# ETH_PHY.net
KiCad netlist of a schematic drawn in Altium Designer
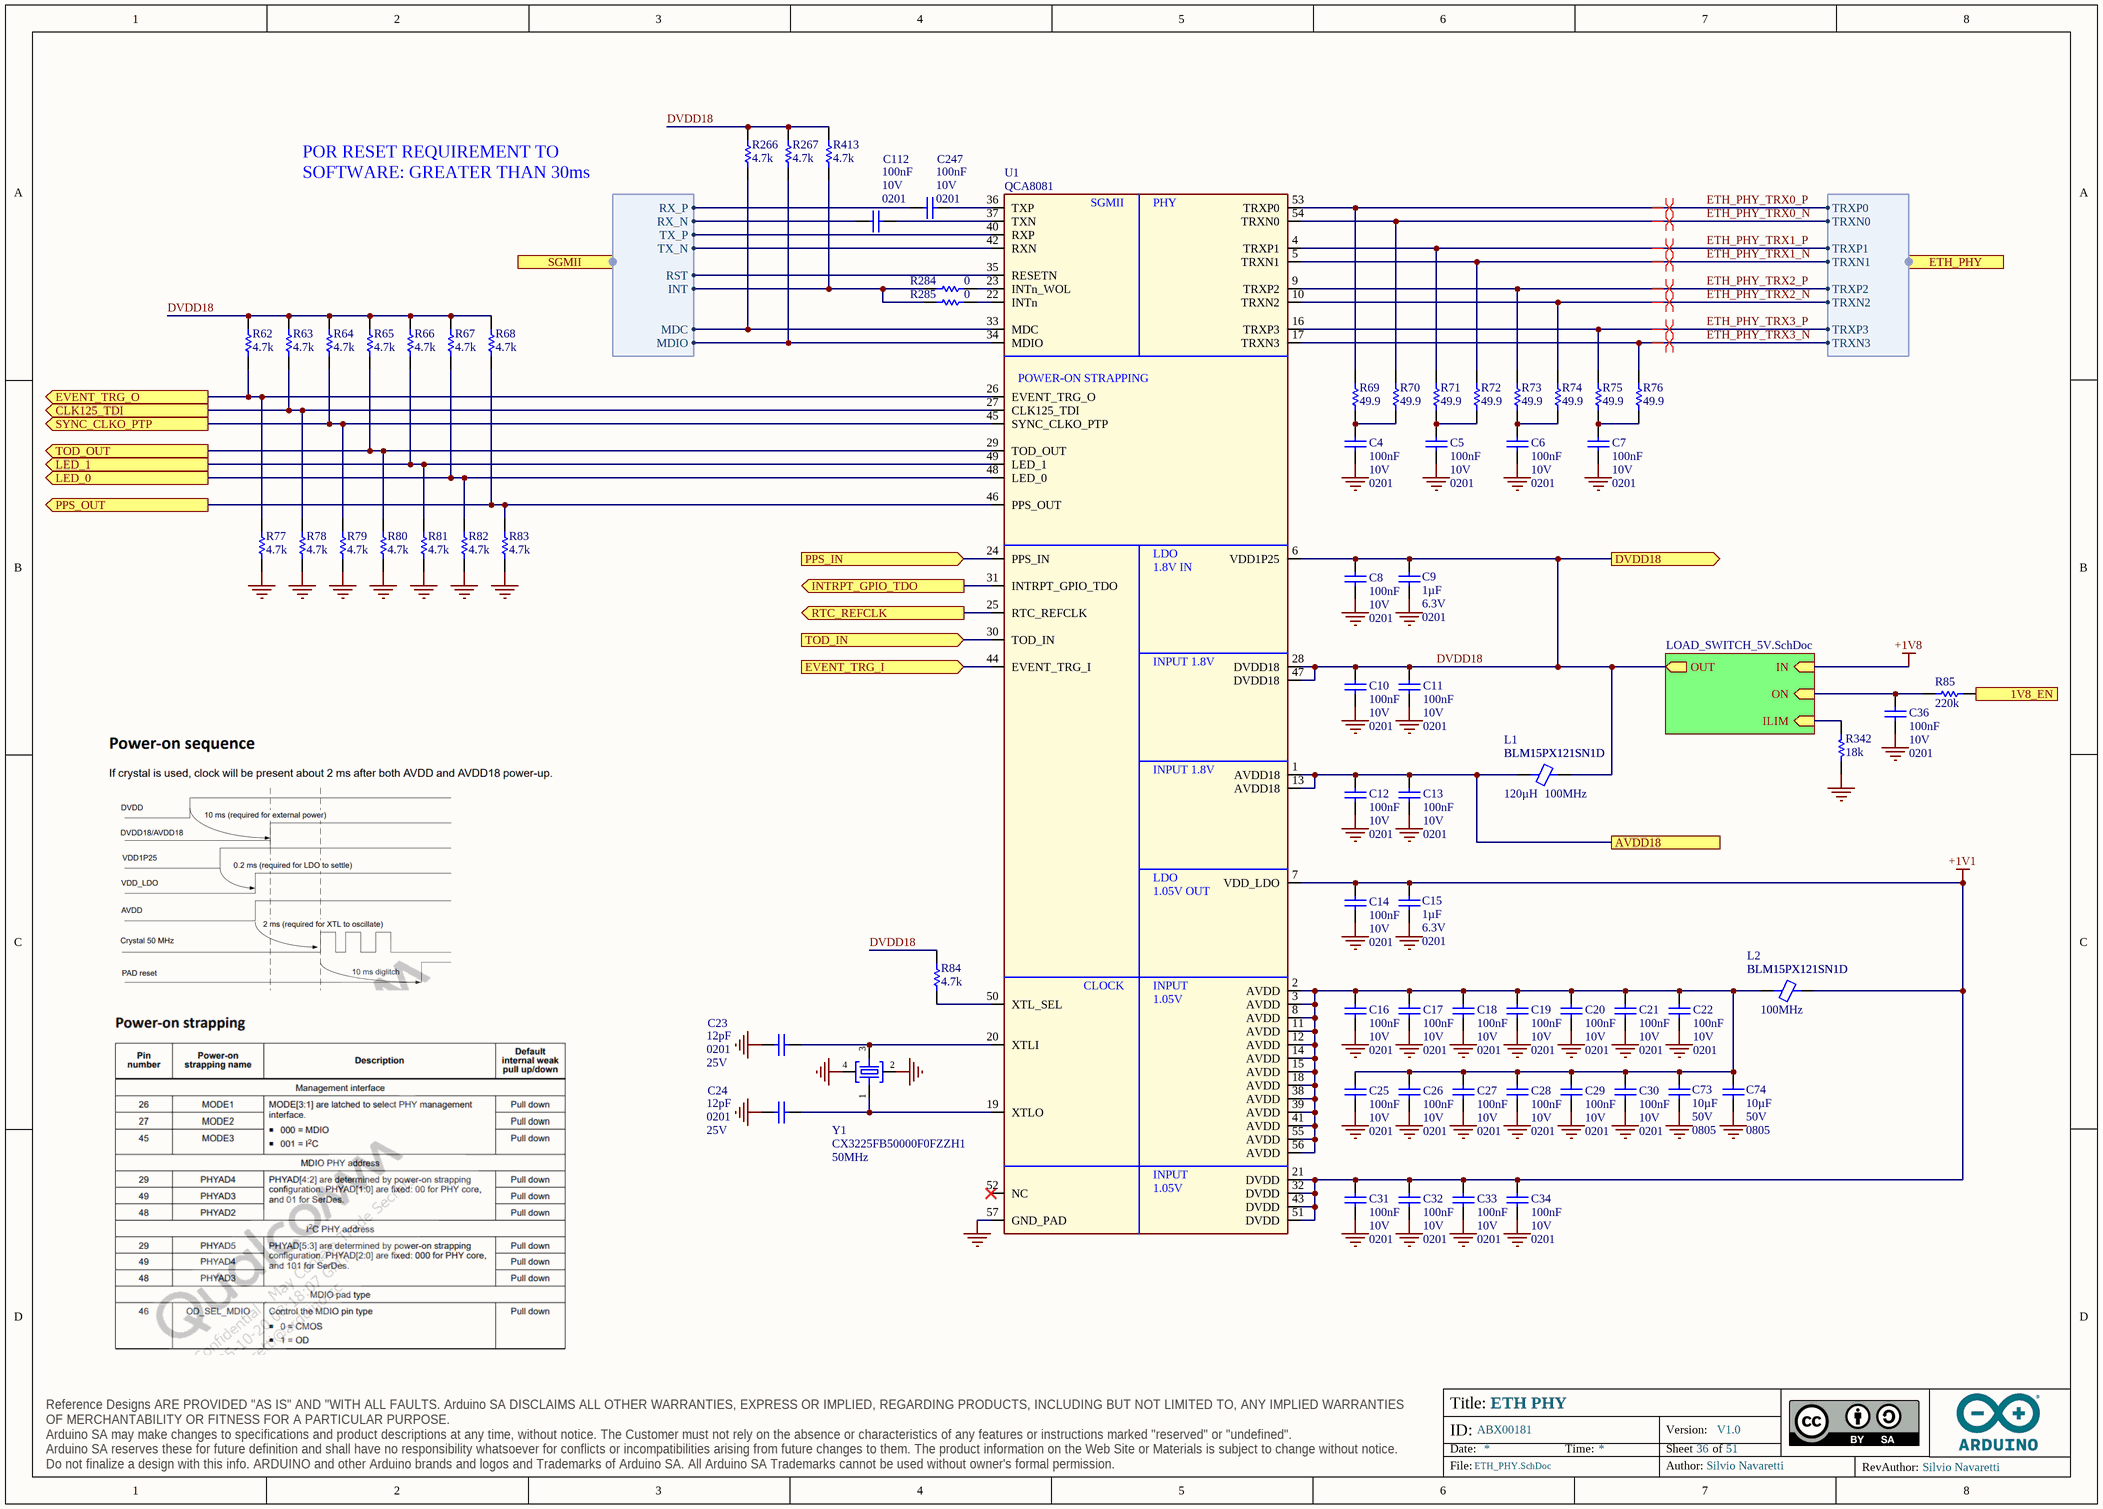
[diagram p0: ETH_PHY.SchDoc]

(export (version "E")
  (design (tool "Eeschema 10.0.6"))
  (components
    (comp (ref "C4")
      (value "100nF")
      (footprint "CAP-0201")
      (description "CAP CHIP 0201 100nF 10% 10V X5R")
      (fields
        (field (name "PART NUMBER") "CL03A104KP3NNNC")
        (field (name "MANUFACTURER") "Samsung Electro-Mechanics")
        (field (name "VOLTAGE") "10V")
        (field (name "CASE CODE (IMPERIAL)") "0201")
      )
      (libsource (lib "Clean") (part "CAP"))
    )
    (comp (ref "C5")
      (value "100nF")
      (footprint "CAP-0201")
      (description "CAP CHIP 0201 100nF 10% 10V X5R")
      (fields
        (field (name "PART NUMBER") "CL03A104KP3NNNC")
        (field (name "MANUFACTURER") "Samsung Electro-Mechanics")
        (field (name "VOLTAGE") "10V")
        (field (name "CASE CODE (IMPERIAL)") "0201")
      )
      (libsource (lib "Clean") (part "CAP"))
    )
    (comp (ref "C6")
      (value "100nF")
      (footprint "CAP-0201")
      (description "CAP CHIP 0201 100nF 10% 10V X5R")
      (fields
        (field (name "PART NUMBER") "CL03A104KP3NNNC")
        (field (name "MANUFACTURER") "Samsung Electro-Mechanics")
        (field (name "VOLTAGE") "10V")
        (field (name "CASE CODE (IMPERIAL)") "0201")
      )
      (libsource (lib "Clean") (part "CAP"))
    )
    (comp (ref "C7")
      (value "100nF")
      (footprint "CAP-0201")
      (description "CAP CHIP 0201 100nF 10% 10V X5R")
      (fields
        (field (name "PART NUMBER") "CL03A104KP3NNNC")
        (field (name "MANUFACTURER") "Samsung Electro-Mechanics")
        (field (name "VOLTAGE") "10V")
        (field (name "CASE CODE (IMPERIAL)") "0201")
      )
      (libsource (lib "Clean") (part "CAP"))
    )
    (comp (ref "C8")
      (value "100nF")
      (footprint "CAP-0201")
      (description "CAP CHIP 0201 100nF 10% 10V X5R")
      (fields
        (field (name "PART NUMBER") "CL03A104KP3NNNC")
        (field (name "MANUFACTURER") "Samsung Electro-Mechanics")
        (field (name "VOLTAGE") "10V")
        (field (name "CASE CODE (IMPERIAL)") "0201")
      )
      (libsource (lib "Clean") (part "CAP"))
    )
    (comp (ref "C9")
      (value "1µF")
      (footprint "CAP-0201")
      (description "CAP CHIP 0201 1uF 20% 6.3V X5R")
      (fields
        (field (name "VOLTAGE") "6.3V")
        (field (name "TOLERANCE") "20%")
        (field (name "PART NUMBER") "GRM033R60J105MEA2D")
        (field (name "CASE CODE (IMPERIAL)") "0201")
      )
      (libsource (lib "Clean") (part "CAP"))
    )
    (comp (ref "C10")
      (value "100nF")
      (footprint "CAP-0201")
      (description "CAP CHIP 0201 100nF 10% 10V X5R")
      (fields
        (field (name "PART NUMBER") "CL03A104KP3NNNC")
        (field (name "MANUFACTURER") "Samsung Electro-Mechanics")
        (field (name "VOLTAGE") "10V")
        (field (name "CASE CODE (IMPERIAL)") "0201")
      )
      (libsource (lib "Clean") (part "CAP"))
    )
    (comp (ref "C11")
      (value "100nF")
      (footprint "CAP-0201")
      (description "CAP CHIP 0201 100nF 10% 10V X5R")
      (fields
        (field (name "PART NUMBER") "CL03A104KP3NNNC")
        (field (name "MANUFACTURER") "Samsung Electro-Mechanics")
        (field (name "VOLTAGE") "10V")
        (field (name "CASE CODE (IMPERIAL)") "0201")
      )
      (libsource (lib "Clean") (part "CAP"))
    )
    (comp (ref "C12")
      (value "100nF")
      (footprint "CAP-0201")
      (description "CAP CHIP 0201 100nF 10% 10V X5R")
      (fields
        (field (name "PART NUMBER") "CL03A104KP3NNNC")
        (field (name "MANUFACTURER") "Samsung Electro-Mechanics")
        (field (name "VOLTAGE") "10V")
        (field (name "CASE CODE (IMPERIAL)") "0201")
      )
      (libsource (lib "Clean") (part "CAP"))
    )
    (comp (ref "C13")
      (value "100nF")
      (footprint "CAP-0201")
      (description "CAP CHIP 0201 100nF 10% 10V X5R")
      (fields
        (field (name "PART NUMBER") "CL03A104KP3NNNC")
        (field (name "MANUFACTURER") "Samsung Electro-Mechanics")
        (field (name "VOLTAGE") "10V")
        (field (name "CASE CODE (IMPERIAL)") "0201")
      )
      (libsource (lib "Clean") (part "CAP"))
    )
    (comp (ref "C14")
      (value "100nF")
      (footprint "CAP-0201")
      (description "CAP CHIP 0201 100nF 10% 10V X5R")
      (fields
        (field (name "PART NUMBER") "CL03A104KP3NNNC")
        (field (name "MANUFACTURER") "Samsung Electro-Mechanics")
        (field (name "VOLTAGE") "10V")
        (field (name "CASE CODE (IMPERIAL)") "0201")
      )
      (libsource (lib "Clean") (part "CAP"))
    )
    (comp (ref "C15")
      (value "1µF")
      (footprint "CAP-0201")
      (description "CAP CHIP 0201 1uF 20% 6.3V X5R")
      (fields
        (field (name "VOLTAGE") "6.3V")
        (field (name "TOLERANCE") "20%")
        (field (name "PART NUMBER") "GRM033R60J105MEA2D")
        (field (name "CASE CODE (IMPERIAL)") "0201")
      )
      (libsource (lib "Clean") (part "CAP"))
    )
    (comp (ref "C16")
      (value "100nF")
      (footprint "CAP-0201")
      (description "CAP CHIP 0201 100nF 10% 10V X5R")
      (fields
        (field (name "PART NUMBER") "CL03A104KP3NNNC")
        (field (name "MANUFACTURER") "Samsung Electro-Mechanics")
        (field (name "VOLTAGE") "10V")
        (field (name "CASE CODE (IMPERIAL)") "0201")
      )
      (libsource (lib "Clean") (part "CAP"))
    )
    (comp (ref "C17")
      (value "100nF")
      (footprint "CAP-0201")
      (description "CAP CHIP 0201 100nF 10% 10V X5R")
      (fields
        (field (name "PART NUMBER") "CL03A104KP3NNNC")
        (field (name "MANUFACTURER") "Samsung Electro-Mechanics")
        (field (name "VOLTAGE") "10V")
        (field (name "CASE CODE (IMPERIAL)") "0201")
      )
      (libsource (lib "Clean") (part "CAP"))
    )
    (comp (ref "C18")
      (value "100nF")
      (footprint "CAP-0201")
      (description "CAP CHIP 0201 100nF 10% 10V X5R")
      (fields
        (field (name "PART NUMBER") "CL03A104KP3NNNC")
        (field (name "MANUFACTURER") "Samsung Electro-Mechanics")
        (field (name "VOLTAGE") "10V")
        (field (name "CASE CODE (IMPERIAL)") "0201")
      )
      (libsource (lib "Clean") (part "CAP"))
    )
    (comp (ref "C19")
      (value "100nF")
      (footprint "CAP-0201")
      (description "CAP CHIP 0201 100nF 10% 10V X5R")
      (fields
        (field (name "PART NUMBER") "CL03A104KP3NNNC")
        (field (name "MANUFACTURER") "Samsung Electro-Mechanics")
        (field (name "VOLTAGE") "10V")
        (field (name "CASE CODE (IMPERIAL)") "0201")
      )
      (libsource (lib "Clean") (part "CAP"))
    )
    (comp (ref "C20")
      (value "100nF")
      (footprint "CAP-0201")
      (description "CAP CHIP 0201 100nF 10% 10V X5R")
      (fields
        (field (name "PART NUMBER") "CL03A104KP3NNNC")
        (field (name "MANUFACTURER") "Samsung Electro-Mechanics")
        (field (name "VOLTAGE") "10V")
        (field (name "CASE CODE (IMPERIAL)") "0201")
      )
      (libsource (lib "Clean") (part "CAP"))
    )
    (comp (ref "C21")
      (value "100nF")
      (footprint "CAP-0201")
      (description "CAP CHIP 0201 100nF 10% 10V X5R")
      (fields
        (field (name "PART NUMBER") "CL03A104KP3NNNC")
        (field (name "MANUFACTURER") "Samsung Electro-Mechanics")
        (field (name "VOLTAGE") "10V")
        (field (name "CASE CODE (IMPERIAL)") "0201")
      )
      (libsource (lib "Clean") (part "CAP"))
    )
    (comp (ref "C22")
      (value "100nF")
      (footprint "CAP-0201")
      (description "CAP CHIP 0201 100nF 10% 10V X5R")
      (fields
        (field (name "PART NUMBER") "CL03A104KP3NNNC")
        (field (name "MANUFACTURER") "Samsung Electro-Mechanics")
        (field (name "VOLTAGE") "10V")
        (field (name "CASE CODE (IMPERIAL)") "0201")
      )
      (libsource (lib "Clean") (part "CAP"))
    )
    (comp (ref "C23")
      (value "12pF")
      (footprint "CAP-0201")
      (description "CAP CHIP 0201 12pF 5% 25V C0G")
      (fields
        (field (name "CASE CODE (IMPERIAL)") "0201")
        (field (name "PART NUMBER") "GRM0335C1E120JA01J")
        (field (name "VOLTAGE") "25V")
        (field (name "TOLERANCE") "5%")
      )
      (libsource (lib "Clean") (part "CAP"))
    )
    (comp (ref "C24")
      (value "12pF")
      (footprint "CAP-0201")
      (description "CAP CHIP 0201 12pF 5% 25V C0G")
      (fields
        (field (name "CASE CODE (IMPERIAL)") "0201")
        (field (name "PART NUMBER") "GRM0335C1E120JA01J")
        (field (name "VOLTAGE") "25V")
        (field (name "TOLERANCE") "5%")
      )
      (libsource (lib "Clean") (part "CAP"))
    )
    (comp (ref "C25")
      (value "100nF")
      (footprint "CAP-0201")
      (description "CAP CHIP 0201 100nF 10% 10V X5R")
      (fields
        (field (name "PART NUMBER") "CL03A104KP3NNNC")
        (field (name "MANUFACTURER") "Samsung Electro-Mechanics")
        (field (name "VOLTAGE") "10V")
        (field (name "CASE CODE (IMPERIAL)") "0201")
      )
      (libsource (lib "Clean") (part "CAP"))
    )
    (comp (ref "C26")
      (value "100nF")
      (footprint "CAP-0201")
      (description "CAP CHIP 0201 100nF 10% 10V X5R")
      (fields
        (field (name "PART NUMBER") "CL03A104KP3NNNC")
        (field (name "MANUFACTURER") "Samsung Electro-Mechanics")
        (field (name "VOLTAGE") "10V")
        (field (name "CASE CODE (IMPERIAL)") "0201")
      )
      (libsource (lib "Clean") (part "CAP"))
    )
    (comp (ref "C27")
      (value "100nF")
      (footprint "CAP-0201")
      (description "CAP CHIP 0201 100nF 10% 10V X5R")
      (fields
        (field (name "PART NUMBER") "CL03A104KP3NNNC")
        (field (name "MANUFACTURER") "Samsung Electro-Mechanics")
        (field (name "VOLTAGE") "10V")
        (field (name "CASE CODE (IMPERIAL)") "0201")
      )
      (libsource (lib "Clean") (part "CAP"))
    )
    (comp (ref "C28")
      (value "100nF")
      (footprint "CAP-0201")
      (description "CAP CHIP 0201 100nF 10% 10V X5R")
      (fields
        (field (name "PART NUMBER") "CL03A104KP3NNNC")
        (field (name "MANUFACTURER") "Samsung Electro-Mechanics")
        (field (name "VOLTAGE") "10V")
        (field (name "CASE CODE (IMPERIAL)") "0201")
      )
      (libsource (lib "Clean") (part "CAP"))
    )
    (comp (ref "C29")
      (value "100nF")
      (footprint "CAP-0201")
      (description "CAP CHIP 0201 100nF 10% 10V X5R")
      (fields
        (field (name "PART NUMBER") "CL03A104KP3NNNC")
        (field (name "MANUFACTURER") "Samsung Electro-Mechanics")
        (field (name "VOLTAGE") "10V")
        (field (name "CASE CODE (IMPERIAL)") "0201")
      )
      (libsource (lib "Clean") (part "CAP"))
    )
    (comp (ref "C30")
      (value "100nF")
      (footprint "CAP-0201")
      (description "CAP CHIP 0201 100nF 10% 10V X5R")
      (fields
        (field (name "PART NUMBER") "CL03A104KP3NNNC")
        (field (name "MANUFACTURER") "Samsung Electro-Mechanics")
        (field (name "VOLTAGE") "10V")
        (field (name "CASE CODE (IMPERIAL)") "0201")
      )
      (libsource (lib "Clean") (part "CAP"))
    )
    (comp (ref "C31")
      (value "100nF")
      (footprint "CAP-0201")
      (description "CAP CHIP 0201 100nF 10% 10V X5R")
      (fields
        (field (name "PART NUMBER") "CL03A104KP3NNNC")
        (field (name "MANUFACTURER") "Samsung Electro-Mechanics")
        (field (name "VOLTAGE") "10V")
        (field (name "CASE CODE (IMPERIAL)") "0201")
      )
      (libsource (lib "Clean") (part "CAP"))
    )
    (comp (ref "C32")
      (value "100nF")
      (footprint "CAP-0201")
      (description "CAP CHIP 0201 100nF 10% 10V X5R")
      (fields
        (field (name "PART NUMBER") "CL03A104KP3NNNC")
        (field (name "MANUFACTURER") "Samsung Electro-Mechanics")
        (field (name "VOLTAGE") "10V")
        (field (name "CASE CODE (IMPERIAL)") "0201")
      )
      (libsource (lib "Clean") (part "CAP"))
    )
    (comp (ref "C33")
      (value "100nF")
      (footprint "CAP-0201")
      (description "CAP CHIP 0201 100nF 10% 10V X5R")
      (fields
        (field (name "PART NUMBER") "CL03A104KP3NNNC")
        (field (name "MANUFACTURER") "Samsung Electro-Mechanics")
        (field (name "VOLTAGE") "10V")
        (field (name "CASE CODE (IMPERIAL)") "0201")
      )
      (libsource (lib "Clean") (part "CAP"))
    )
    (comp (ref "C34")
      (value "100nF")
      (footprint "CAP-0201")
      (description "CAP CHIP 0201 100nF 10% 10V X5R")
      (fields
        (field (name "PART NUMBER") "CL03A104KP3NNNC")
        (field (name "MANUFACTURER") "Samsung Electro-Mechanics")
        (field (name "VOLTAGE") "10V")
        (field (name "CASE CODE (IMPERIAL)") "0201")
      )
      (libsource (lib "Clean") (part "CAP"))
    )
    (comp (ref "C36")
      (value "100nF")
      (footprint "CAP-0201")
      (description "CAP CHIP 0201 100nF 10% 10V X5R")
      (fields
        (field (name "PART NUMBER") "CL03A104KP3NNNC")
        (field (name "MANUFACTURER") "Samsung Electro-Mechanics")
        (field (name "VOLTAGE") "10V")
        (field (name "CASE CODE (IMPERIAL)") "0201")
      )
      (libsource (lib "Clean") (part "CAP"))
    )
    (comp (ref "C73")
      (value "10µF")
      (footprint "CAP-0805")
      (description "CAP CHIP 0805 10uF 20% 50V X5R")
      (fields
        (field (name "MANUFACTURER") "Murata Electronics")
        (field (name "VOLTAGE") "50V")
        (field (name "TOLERANCE") "20%")
        (field (name "CASE CODE (IMPERIAL)") "0805")
      )
      (libsource (lib "Clean") (part "CAP"))
    )
    (comp (ref "C74")
      (value "10µF")
      (footprint "CAP-0805")
      (description "CAP CHIP 0805 10uF 20% 50V X5R")
      (fields
        (field (name "MANUFACTURER") "Murata Electronics")
        (field (name "VOLTAGE") "50V")
        (field (name "TOLERANCE") "20%")
        (field (name "CASE CODE (IMPERIAL)") "0805")
      )
      (libsource (lib "Clean") (part "CAP"))
    )
    (comp (ref "C112")
      (value "100nF")
      (footprint "CAP-0201")
      (description "CAP CHIP 0201 100nF 10% 10V X5R")
      (fields
        (field (name "PART NUMBER") "CL03A104KP3NNNC")
        (field (name "MANUFACTURER") "Samsung Electro-Mechanics")
        (field (name "VOLTAGE") "10V")
        (field (name "CASE CODE (IMPERIAL)") "0201")
      )
      (libsource (lib "Clean") (part "CAP"))
    )
    (comp (ref "C247")
      (value "100nF")
      (footprint "CAP-0201")
      (description "CAP CHIP 0201 100nF 10% 10V X5R")
      (fields
        (field (name "PART NUMBER") "CL03A104KP3NNNC")
        (field (name "MANUFACTURER") "Samsung Electro-Mechanics")
        (field (name "VOLTAGE") "10V")
        (field (name "CASE CODE (IMPERIAL)") "0201")
      )
      (libsource (lib "Clean") (part "CAP"))
    )
    (comp (ref "L1")
      (value "BLM15PX121SN1D")
      (footprint "L-0402")
      (description "FERRITE SMD 0402 120Ohm 25% 100MHz Ferrite 2A")
      (fields
        (field (name "PART NUMBER") "BLM15PX121SN1D")
        (field (name "INDUCTANCE") "120µH")
        (field (name "TEST FREQUENCY") "100MHz")
        (field (name "MANUFACTURER") "Murata")
        (field (name "TOLERANCE") "25%")
      )
      (libsource (lib "Clean") (part "Ferrite"))
    )
    (comp (ref "L2")
      (value "BLM15PX121SN1D")
      (footprint "L-0402")
      (description "FERRITE SMD 0402 120Ohm 25% 100MHz Ferrite 2A")
      (fields
        (field (name "PART NUMBER") "BLM15PX121SN1D")
        (field (name "TEST FREQUENCY") "100MHz")
        (field (name "MANUFACTURER") "Murata")
        (field (name "TOLERANCE") "25%")
      )
      (libsource (lib "Clean") (part "Ferrite"))
    )
    (comp (ref "R62")
      (value "4.7k")
      (footprint "RES-0201")
      (description "RES CHIP 0201 4k7 1% 1/20W")
      (fields (field (name "POWER") "50mW") (field (name "PART NUMBER") "RC0201FR-074K7L"))
      (libsource (lib "Clean") (part "RES"))
    )
    (comp (ref "R63")
      (value "4.7k")
      (footprint "RES-0201")
      (description "RES CHIP 0201 4k7 1% 1/20W")
      (fields (field (name "POWER") "50mW") (field (name "PART NUMBER") "RC0201FR-074K7L"))
      (libsource (lib "Clean") (part "RES"))
    )
    (comp (ref "R64")
      (value "4.7k")
      (footprint "RES-0201")
      (description "RES CHIP 0201 4k7 1% 1/20W")
      (fields (field (name "POWER") "50mW") (field (name "PART NUMBER") "RC0201FR-074K7L"))
      (libsource (lib "Clean") (part "RES"))
    )
    (comp (ref "R65")
      (value "4.7k")
      (footprint "RES-0201")
      (description "RES CHIP 0201 4k7 1% 1/20W")
      (fields (field (name "POWER") "50mW") (field (name "PART NUMBER") "RC0201FR-074K7L"))
      (libsource (lib "Clean") (part "RES"))
    )
    (comp (ref "R66")
      (value "4.7k")
      (footprint "RES-0201")
      (description "RES CHIP 0201 4k7 1% 1/20W")
      (fields (field (name "POWER") "50mW") (field (name "PART NUMBER") "RC0201FR-074K7L"))
      (libsource (lib "Clean") (part "RES"))
    )
    (comp (ref "R67")
      (value "4.7k")
      (footprint "RES-0201")
      (description "RES CHIP 0201 4k7 1% 1/20W")
      (fields (field (name "POWER") "50mW") (field (name "PART NUMBER") "RC0201FR-074K7L"))
      (libsource (lib "Clean") (part "RES"))
    )
    (comp (ref "R68")
      (value "4.7k")
      (footprint "RES-0201")
      (description "RES CHIP 0201 4k7 1% 1/20W")
      (fields (field (name "POWER") "50mW") (field (name "PART NUMBER") "RC0201FR-074K7L"))
      (libsource (lib "Clean") (part "RES"))
    )
    (comp (ref "R69")
      (value "49.9")
      (footprint "RES-0201")
      (description "RES CHIP 0201 49R9 1% 1/20W")
      (fields (field (name "MANUFACTURER") "Yageo") (field (name "POWER") "50mW"))
      (libsource (lib "Clean") (part "RES"))
    )
    (comp (ref "R70")
      (value "49.9")
      (footprint "RES-0201")
      (description "RES CHIP 0201 49R9 1% 1/20W")
      (fields (field (name "MANUFACTURER") "Yageo") (field (name "POWER") "50mW"))
      (libsource (lib "Clean") (part "RES"))
    )
    (comp (ref "R71")
      (value "49.9")
      (footprint "RES-0201")
      (description "RES CHIP 0201 49R9 1% 1/20W")
      (fields (field (name "MANUFACTURER") "Yageo") (field (name "POWER") "50mW"))
      (libsource (lib "Clean") (part "RES"))
    )
    (comp (ref "R72")
      (value "49.9")
      (footprint "RES-0201")
      (description "RES CHIP 0201 49R9 1% 1/20W")
      (fields (field (name "MANUFACTURER") "Yageo") (field (name "POWER") "50mW"))
      (libsource (lib "Clean") (part "RES"))
    )
    (comp (ref "R73")
      (value "49.9")
      (footprint "RES-0201")
      (description "RES CHIP 0201 49R9 1% 1/20W")
      (fields (field (name "MANUFACTURER") "Yageo") (field (name "POWER") "50mW"))
      (libsource (lib "Clean") (part "RES"))
    )
    (comp (ref "R74")
      (value "49.9")
      (footprint "RES-0201")
      (description "RES CHIP 0201 49R9 1% 1/20W")
      (fields (field (name "MANUFACTURER") "Yageo") (field (name "POWER") "50mW"))
      (libsource (lib "Clean") (part "RES"))
    )
    (comp (ref "R75")
      (value "49.9")
      (footprint "RES-0201")
      (description "RES CHIP 0201 49R9 1% 1/20W")
      (fields (field (name "MANUFACTURER") "Yageo") (field (name "POWER") "50mW"))
      (libsource (lib "Clean") (part "RES"))
    )
    (comp (ref "R76")
      (value "49.9")
      (footprint "RES-0201")
      (description "RES CHIP 0201 49R9 1% 1/20W")
      (fields (field (name "MANUFACTURER") "Yageo") (field (name "POWER") "50mW"))
      (libsource (lib "Clean") (part "RES"))
    )
    (comp (ref "R77")
      (value "4.7k")
      (footprint "RES-0201")
      (description "RES CHIP 0201 4k7 1% 1/20W")
      (fields (field (name "POWER") "50mW") (field (name "PART NUMBER") "RC0201FR-074K7L"))
      (libsource (lib "Clean") (part "RES"))
    )
    (comp (ref "R78")
      (value "4.7k")
      (footprint "RES-0201")
      (description "RES CHIP 0201 4k7 1% 1/20W")
      (fields (field (name "POWER") "50mW") (field (name "PART NUMBER") "RC0201FR-074K7L"))
      (libsource (lib "Clean") (part "RES"))
    )
    (comp (ref "R79")
      (value "4.7k")
      (footprint "RES-0201")
      (description "RES CHIP 0201 4k7 1% 1/20W")
      (fields (field (name "POWER") "50mW") (field (name "PART NUMBER") "RC0201FR-074K7L"))
      (libsource (lib "Clean") (part "RES"))
    )
    (comp (ref "R80")
      (value "4.7k")
      (footprint "RES-0201")
      (description "RES CHIP 0201 4k7 1% 1/20W")
      (fields (field (name "POWER") "50mW") (field (name "PART NUMBER") "RC0201FR-074K7L"))
      (libsource (lib "Clean") (part "RES"))
    )
    (comp (ref "R81")
      (value "4.7k")
      (footprint "RES-0201")
      (description "RES CHIP 0201 4k7 1% 1/20W")
      (fields (field (name "POWER") "50mW") (field (name "PART NUMBER") "RC0201FR-074K7L"))
      (libsource (lib "Clean") (part "RES"))
    )
    (comp (ref "R82")
      (value "4.7k")
      (footprint "RES-0201")
      (description "RES CHIP 0201 4k7 1% 1/20W")
      (fields (field (name "POWER") "50mW") (field (name "PART NUMBER") "RC0201FR-074K7L"))
      (libsource (lib "Clean") (part "RES"))
    )
    (comp (ref "R83")
      (value "4.7k")
      (footprint "RES-0201")
      (description "RES CHIP 0201 4k7 1% 1/20W")
      (fields (field (name "POWER") "50mW") (field (name "PART NUMBER") "RC0201FR-074K7L"))
      (libsource (lib "Clean") (part "RES"))
    )
    (comp (ref "R84")
      (value "4.7k")
      (footprint "RES-0201")
      (description "RES CHIP 0201 4k7 1% 1/20W")
      (fields (field (name "POWER") "50mW") (field (name "PART NUMBER") "RC0201FR-074K7L"))
      (libsource (lib "Clean") (part "RES"))
    )
    (comp (ref "R85")
      (value "220k")
      (footprint "RES-0201")
      (description "RES CHIP 0201 220k 1% 1/20W")
      (fields (field (name "PART NUMBER") "AC0201FR-07220KL") (field (name "TOLERANCE") "1%"))
      (libsource (lib "Clean") (part "RES"))
    )
    (comp (ref "R266")
      (value "4.7k")
      (footprint "RES-0201")
      (description "RES CHIP 0201 4k7 1% 1/20W")
      (fields (field (name "POWER") "50mW") (field (name "PART NUMBER") "RC0201FR-074K7L"))
      (libsource (lib "Clean") (part "RES"))
    )
    (comp (ref "R267")
      (value "4.7k")
      (footprint "RES-0201")
      (description "RES CHIP 0201 4k7 1% 1/20W")
      (fields (field (name "POWER") "50mW") (field (name "PART NUMBER") "RC0201FR-074K7L"))
      (libsource (lib "Clean") (part "RES"))
    )
    (comp (ref "R284")
      (value "0")
      (footprint "RES-0201")
      (description "RES CHIP 0201 0R")
      (fields (field (name "MANUFACTURER") "Vishay") (field (name "PART NUMBER") "CRCW02010000Z0ED"))
      (libsource (lib "Clean") (part "RES"))
    )
    (comp (ref "R285")
      (value "0")
      (footprint "RES-0201")
      (description "RES CHIP 0201 0R")
      (fields (field (name "MANUFACTURER") "Vishay") (field (name "PART NUMBER") "CRCW02010000Z0ED"))
      (libsource (lib "Clean") (part "RES"))
    )
    (comp (ref "R342")
      (value "18k")
      (footprint "RES-0201")
      (description "RES CHIP 0201 18k 1% 1/20W")
      (fields (field (name "POWER") "50mW") (field (name "TOLERANCE") "1%"))
      (libsource (lib "Clean") (part "RES"))
    )
    (comp (ref "R413")
      (value "4.7k")
      (footprint "RES-0201")
      (description "RES CHIP 0201 4k7 1% 1/20W")
      (fields (field (name "POWER") "50mW") (field (name "PART NUMBER") "RC0201FR-074K7L"))
      (libsource (lib "Clean") (part "RES"))
    )
    (comp (ref "U1")
      (value "QCA8081")
      (footprint "Qualcomm QCA8081 56 MQFN 7x7mm pitch 0.4mm")
      (description "IC ETH PHY 2.5Gb, 7x7mm MQFN56")
      (fields (field (name "MANUFACTURER") "Qualcomm"))
      (libsource (lib "Clean") (part "QCA8081-Symbol-1"))
    )
    (comp (ref "Y1")
      (value "CX3225FB50000F0FZZH1")
      (footprint "CRYSTAL3.2X2.5")
      (description "CRYSTAL 50MHz tolerance 10ppm stability 20ppm load 10pF 3.2x2.5mm")
      (fields (field (name "FREQUENCY") "50MHz") (field (name "MANUFACTURER") "Kyocera"))
      (libsource (lib "Clean") (part "Crystal"))
    )
  )
  (nets
    (net (code "3") (name "+1V1") (class "Default")
      (node (ref "C14") (pin "2") (pinfunction "2_2") (pintype "passive"))
      (node (ref "C15") (pin "2") (pinfunction "2_2") (pintype "passive"))
      (node (ref "C31") (pin "2") (pinfunction "2_2") (pintype "passive"))
      (node (ref "C32") (pin "2") (pinfunction "2_2") (pintype "passive"))
      (node (ref "C33") (pin "2") (pinfunction "2_2") (pintype "passive"))
      (node (ref "C34") (pin "2") (pinfunction "2_2") (pintype "passive"))
      (node (ref "L2") (pin "2") (pinfunction "2_2") (pintype "passive"))
      (node (ref "U1") (pin "21") (pinfunction "DVDD_21") (pintype "passive"))
      (node (ref "U1") (pin "32") (pinfunction "DVDD_32") (pintype "passive"))
      (node (ref "U1") (pin "43") (pinfunction "DVDD_43") (pintype "passive"))
      (node (ref "U1") (pin "51") (pinfunction "DVDD_51") (pintype "passive"))
      (node (ref "U1") (pin "7") (pinfunction "VDD_LDO_7") (pintype "passive"))
    )
    (net (code "5") (name "/1V8_EN") (class "Default")
      (node (ref "R85") (pin "1") (pinfunction "1_1") (pintype "passive"))
    )
    (net (code "6") (name "/AVDD18") (class "Default")
      (node (ref "C12") (pin "2") (pinfunction "2_2") (pintype "passive"))
      (node (ref "C13") (pin "2") (pinfunction "2_2") (pintype "passive"))
      (node (ref "L1") (pin "1") (pinfunction "1_1") (pintype "passive"))
      (node (ref "U1") (pin "1") (pinfunction "AVDD18_1") (pintype "passive"))
      (node (ref "U1") (pin "13") (pinfunction "AVDD18_13") (pintype "passive"))
    )
    (net (code "7") (name "/CLK125_TDI") (class "Default")
      (node (ref "R63") (pin "1") (pinfunction "1_1") (pintype "passive"))
      (node (ref "R78") (pin "2") (pinfunction "2_2") (pintype "passive"))
      (node (ref "U1") (pin "27") (pinfunction "CLK125_TDI_27") (pintype "passive"))
    )
    (net (code "8") (name "/DVDD18") (class "Default")
      (node (ref "C10") (pin "2") (pinfunction "2_2") (pintype "passive"))
      (node (ref "C11") (pin "2") (pinfunction "2_2") (pintype "passive"))
      (node (ref "C8") (pin "2") (pinfunction "2_2") (pintype "passive"))
      (node (ref "C9") (pin "2") (pinfunction "2_2") (pintype "passive"))
      (node (ref "L1") (pin "2") (pinfunction "2_2") (pintype "passive"))
      (node (ref "R266") (pin "2") (pinfunction "2_2") (pintype "passive"))
      (node (ref "R267") (pin "2") (pinfunction "2_2") (pintype "passive"))
      (node (ref "R413") (pin "2") (pinfunction "2_2") (pintype "passive"))
      (node (ref "R62") (pin "2") (pinfunction "2_2") (pintype "passive"))
      (node (ref "R63") (pin "2") (pinfunction "2_2") (pintype "passive"))
      (node (ref "R64") (pin "2") (pinfunction "2_2") (pintype "passive"))
      (node (ref "R65") (pin "2") (pinfunction "2_2") (pintype "passive"))
      (node (ref "R66") (pin "2") (pinfunction "2_2") (pintype "passive"))
      (node (ref "R67") (pin "2") (pinfunction "2_2") (pintype "passive"))
      (node (ref "R68") (pin "2") (pinfunction "2_2") (pintype "passive"))
      (node (ref "R84") (pin "2") (pinfunction "2_2") (pintype "passive"))
      (node (ref "U1") (pin "28") (pinfunction "DVDD18_28") (pintype "passive"))
      (node (ref "U1") (pin "47") (pinfunction "DVDD18_47") (pintype "passive"))
      (node (ref "U1") (pin "6") (pinfunction "VDD1P25_6") (pintype "passive"))
    )
    (net (code "9") (name "/ETH_PHY_TRX0_N") (class "Default")
      (node (ref "R70") (pin "2") (pinfunction "2_2") (pintype "passive"))
      (node (ref "U1") (pin "54") (pinfunction "TRXN0_54") (pintype "passive"))
    )
    (net (code "10") (name "/ETH_PHY_TRX0_P") (class "Default")
      (node (ref "R69") (pin "2") (pinfunction "2_2") (pintype "passive"))
      (node (ref "U1") (pin "53") (pinfunction "TRXP0_53") (pintype "passive"))
    )
    (net (code "11") (name "/ETH_PHY_TRX1_N") (class "Default")
      (node (ref "R72") (pin "2") (pinfunction "2_2") (pintype "passive"))
      (node (ref "U1") (pin "5") (pinfunction "TRXN1_5") (pintype "passive"))
    )
    (net (code "12") (name "/ETH_PHY_TRX1_P") (class "Default")
      (node (ref "R71") (pin "2") (pinfunction "2_2") (pintype "passive"))
      (node (ref "U1") (pin "4") (pinfunction "TRXP1_4") (pintype "passive"))
    )
    (net (code "13") (name "/ETH_PHY_TRX2_N") (class "Default")
      (node (ref "R74") (pin "2") (pinfunction "2_2") (pintype "passive"))
      (node (ref "U1") (pin "10") (pinfunction "TRXN2_10") (pintype "passive"))
    )
    (net (code "14") (name "/ETH_PHY_TRX2_P") (class "Default")
      (node (ref "R73") (pin "2") (pinfunction "2_2") (pintype "passive"))
      (node (ref "U1") (pin "9") (pinfunction "TRXP2_9") (pintype "passive"))
    )
    (net (code "15") (name "/ETH_PHY_TRX3_N") (class "Default")
      (node (ref "R76") (pin "2") (pinfunction "2_2") (pintype "passive"))
      (node (ref "U1") (pin "17") (pinfunction "TRXN3_17") (pintype "passive"))
    )
    (net (code "16") (name "/ETH_PHY_TRX3_P") (class "Default")
      (node (ref "R75") (pin "2") (pinfunction "2_2") (pintype "passive"))
      (node (ref "U1") (pin "16") (pinfunction "TRXP3_16") (pintype "passive"))
    )
    (net (code "17") (name "/EVENT_TRG_I") (class "Default")
      (node (ref "U1") (pin "44") (pinfunction "EVENT_TRG_I_44") (pintype "passive"))
    )
    (net (code "18") (name "/EVENT_TRG_O") (class "Default")
      (node (ref "R62") (pin "1") (pinfunction "1_1") (pintype "passive"))
      (node (ref "R77") (pin "2") (pinfunction "2_2") (pintype "passive"))
      (node (ref "U1") (pin "26") (pinfunction "EVENT_TRG_O_26") (pintype "passive"))
    )
    (net (code "19") (name "/ILIM") (class "Default")
      (node (ref "R342") (pin "2") (pinfunction "2_2") (pintype "passive"))
    )
    (net (code "20") (name "/INT") (class "Default")
      (node (ref "R284") (pin "1") (pinfunction "1_1") (pintype "passive"))
      (node (ref "R285") (pin "1") (pinfunction "1_1") (pintype "passive"))
      (node (ref "R413") (pin "1") (pinfunction "1_1") (pintype "passive"))
    )
    (net (code "21") (name "/INTRPT_GPIO_TDO") (class "Default")
      (node (ref "U1") (pin "31") (pinfunction "INTRPT_GPIO_TDO_31") (pintype "passive"))
    )
    (net (code "22") (name "/LED_0") (class "Default")
      (node (ref "R67") (pin "1") (pinfunction "1_1") (pintype "passive"))
      (node (ref "R82") (pin "2") (pinfunction "2_2") (pintype "passive"))
      (node (ref "U1") (pin "48") (pinfunction "LED_0_48") (pintype "passive"))
    )
    (net (code "23") (name "/LED_1") (class "Default")
      (node (ref "R66") (pin "1") (pinfunction "1_1") (pintype "passive"))
      (node (ref "R81") (pin "2") (pinfunction "2_2") (pintype "passive"))
      (node (ref "U1") (pin "49") (pinfunction "LED_1_49") (pintype "passive"))
    )
    (net (code "24") (name "/MDC") (class "Default")
      (node (ref "R266") (pin "1") (pinfunction "1_1") (pintype "passive"))
      (node (ref "U1") (pin "33") (pinfunction "MDC_33") (pintype "passive"))
    )
    (net (code "25") (name "/MDIO") (class "Default")
      (node (ref "R267") (pin "1") (pinfunction "1_1") (pintype "passive"))
      (node (ref "U1") (pin "34") (pinfunction "MDIO_34") (pintype "passive"))
    )
    (net (code "26") (name "/ON") (class "Default")
      (node (ref "C36") (pin "2") (pinfunction "2_2") (pintype "passive"))
      (node (ref "R85") (pin "2") (pinfunction "2_2") (pintype "passive"))
    )
    (net (code "27") (name "/PPS_IN") (class "Default")
      (node (ref "U1") (pin "24") (pinfunction "PPS_IN_24") (pintype "passive"))
    )
    (net (code "28") (name "/PPS_OUT") (class "Default")
      (node (ref "R68") (pin "1") (pinfunction "1_1") (pintype "passive"))
      (node (ref "R83") (pin "2") (pinfunction "2_2") (pintype "passive"))
      (node (ref "U1") (pin "46") (pinfunction "PPS_OUT_46") (pintype "passive"))
    )
    (net (code "29") (name "/RST") (class "Default")
      (node (ref "U1") (pin "35") (pinfunction "RESETN_35") (pintype "passive"))
    )
    (net (code "30") (name "/RTC_REFCLK") (class "Default")
      (node (ref "U1") (pin "25") (pinfunction "RTC_REFCLK_25") (pintype "passive"))
    )
    (net (code "31") (name "/RX_N") (class "Default")
      (node (ref "C112") (pin "2") (pinfunction "2_2") (pintype "passive"))
    )
    (net (code "32") (name "/RX_P") (class "Default")
      (node (ref "C247") (pin "2") (pinfunction "2_2") (pintype "passive"))
    )
    (net (code "33") (name "/SYNC_CLKO_PTP") (class "Default")
      (node (ref "R64") (pin "1") (pinfunction "1_1") (pintype "passive"))
      (node (ref "R79") (pin "2") (pinfunction "2_2") (pintype "passive"))
      (node (ref "U1") (pin "45") (pinfunction "SYNC_CLKO_PTP_45") (pintype "passive"))
    )
    (net (code "34") (name "/TOD_IN") (class "Default")
      (node (ref "U1") (pin "30") (pinfunction "TOD_IN_30") (pintype "passive"))
    )
    (net (code "35") (name "/TOD_OUT") (class "Default")
      (node (ref "R65") (pin "1") (pinfunction "1_1") (pintype "passive"))
      (node (ref "R80") (pin "2") (pinfunction "2_2") (pintype "passive"))
      (node (ref "U1") (pin "29") (pinfunction "TOD_OUT_29") (pintype "passive"))
    )
    (net (code "36") (name "/TX_N") (class "Default")
      (node (ref "U1") (pin "42") (pinfunction "RXN_42") (pintype "passive"))
    )
    (net (code "37") (name "/TX_P") (class "Default")
      (node (ref "U1") (pin "40") (pinfunction "RXP_40") (pintype "passive"))
    )
    (net (code "40") (name "GND") (class "Default")
      (node (ref "C10") (pin "1") (pinfunction "1_1") (pintype "passive"))
      (node (ref "C11") (pin "1") (pinfunction "1_1") (pintype "passive"))
      (node (ref "C12") (pin "1") (pinfunction "1_1") (pintype "passive"))
      (node (ref "C13") (pin "1") (pinfunction "1_1") (pintype "passive"))
      (node (ref "C14") (pin "1") (pinfunction "1_1") (pintype "passive"))
      (node (ref "C15") (pin "1") (pinfunction "1_1") (pintype "passive"))
      (node (ref "C16") (pin "1") (pinfunction "1_1") (pintype "passive"))
      (node (ref "C17") (pin "1") (pinfunction "1_1") (pintype "passive"))
      (node (ref "C18") (pin "1") (pinfunction "1_1") (pintype "passive"))
      (node (ref "C19") (pin "1") (pinfunction "1_1") (pintype "passive"))
      (node (ref "C20") (pin "1") (pinfunction "1_1") (pintype "passive"))
      (node (ref "C21") (pin "1") (pinfunction "1_1") (pintype "passive"))
      (node (ref "C22") (pin "1") (pinfunction "1_1") (pintype "passive"))
      (node (ref "C23") (pin "2") (pinfunction "2_2") (pintype "passive"))
      (node (ref "C24") (pin "2") (pinfunction "2_2") (pintype "passive"))
      (node (ref "C25") (pin "1") (pinfunction "1_1") (pintype "passive"))
      (node (ref "C26") (pin "1") (pinfunction "1_1") (pintype "passive"))
      (node (ref "C27") (pin "1") (pinfunction "1_1") (pintype "passive"))
      (node (ref "C28") (pin "1") (pinfunction "1_1") (pintype "passive"))
      (node (ref "C29") (pin "1") (pinfunction "1_1") (pintype "passive"))
      (node (ref "C30") (pin "1") (pinfunction "1_1") (pintype "passive"))
      (node (ref "C31") (pin "1") (pinfunction "1_1") (pintype "passive"))
      (node (ref "C32") (pin "1") (pinfunction "1_1") (pintype "passive"))
      (node (ref "C33") (pin "1") (pinfunction "1_1") (pintype "passive"))
      (node (ref "C34") (pin "1") (pinfunction "1_1") (pintype "passive"))
      (node (ref "C36") (pin "1") (pinfunction "1_1") (pintype "passive"))
      (node (ref "C4") (pin "1") (pinfunction "1_1") (pintype "passive"))
      (node (ref "C5") (pin "1") (pinfunction "1_1") (pintype "passive"))
      (node (ref "C6") (pin "1") (pinfunction "1_1") (pintype "passive"))
      (node (ref "C7") (pin "1") (pinfunction "1_1") (pintype "passive"))
      (node (ref "C73") (pin "2") (pinfunction "2_2") (pintype "passive"))
      (node (ref "C74") (pin "2") (pinfunction "2_2") (pintype "passive"))
      (node (ref "C8") (pin "1") (pinfunction "1_1") (pintype "passive"))
      (node (ref "C9") (pin "1") (pinfunction "1_1") (pintype "passive"))
      (node (ref "R342") (pin "1") (pinfunction "1_1") (pintype "passive"))
      (node (ref "R77") (pin "1") (pinfunction "1_1") (pintype "passive"))
      (node (ref "R78") (pin "1") (pinfunction "1_1") (pintype "passive"))
      (node (ref "R79") (pin "1") (pinfunction "1_1") (pintype "passive"))
      (node (ref "R80") (pin "1") (pinfunction "1_1") (pintype "passive"))
      (node (ref "R81") (pin "1") (pinfunction "1_1") (pintype "passive"))
      (node (ref "R82") (pin "1") (pinfunction "1_1") (pintype "passive"))
      (node (ref "R83") (pin "1") (pinfunction "1_1") (pintype "passive"))
      (node (ref "U1") (pin "57") (pinfunction "GND_PAD_57") (pintype "passive"))
      (node (ref "Y1") (pin "2") (pinfunction "2_2") (pintype "passive"))
      (node (ref "Y1") (pin "4") (pinfunction "4_4") (pintype "passive"))
    )
    (net (code "41") (name "Net-(C4-Pad2)") (class "Default")
      (node (ref "C4") (pin "2") (pinfunction "2_2") (pintype "passive"))
      (node (ref "R69") (pin "1") (pinfunction "1_1") (pintype "passive"))
      (node (ref "R70") (pin "1") (pinfunction "1_1") (pintype "passive"))
    )
    (net (code "42") (name "Net-(C5-Pad2)") (class "Default")
      (node (ref "C5") (pin "2") (pinfunction "2_2") (pintype "passive"))
      (node (ref "R71") (pin "1") (pinfunction "1_1") (pintype "passive"))
      (node (ref "R72") (pin "1") (pinfunction "1_1") (pintype "passive"))
    )
    (net (code "43") (name "Net-(C6-Pad2)") (class "Default")
      (node (ref "C6") (pin "2") (pinfunction "2_2") (pintype "passive"))
      (node (ref "R73") (pin "1") (pinfunction "1_1") (pintype "passive"))
      (node (ref "R74") (pin "1") (pinfunction "1_1") (pintype "passive"))
    )
    (net (code "44") (name "Net-(C7-Pad2)") (class "Default")
      (node (ref "C7") (pin "2") (pinfunction "2_2") (pintype "passive"))
      (node (ref "R75") (pin "1") (pinfunction "1_1") (pintype "passive"))
      (node (ref "R76") (pin "1") (pinfunction "1_1") (pintype "passive"))
    )
    (net (code "45") (name "Net-(C16-Pad2)") (class "Default")
      (node (ref "C16") (pin "2") (pinfunction "2_2") (pintype "passive"))
      (node (ref "C17") (pin "2") (pinfunction "2_2") (pintype "passive"))
      (node (ref "C18") (pin "2") (pinfunction "2_2") (pintype "passive"))
      (node (ref "C19") (pin "2") (pinfunction "2_2") (pintype "passive"))
      (node (ref "C20") (pin "2") (pinfunction "2_2") (pintype "passive"))
      (node (ref "C21") (pin "2") (pinfunction "2_2") (pintype "passive"))
      (node (ref "C22") (pin "2") (pinfunction "2_2") (pintype "passive"))
      (node (ref "C25") (pin "2") (pinfunction "2_2") (pintype "passive"))
      (node (ref "C26") (pin "2") (pinfunction "2_2") (pintype "passive"))
      (node (ref "C27") (pin "2") (pinfunction "2_2") (pintype "passive"))
      (node (ref "C28") (pin "2") (pinfunction "2_2") (pintype "passive"))
      (node (ref "C29") (pin "2") (pinfunction "2_2") (pintype "passive"))
      (node (ref "C30") (pin "2") (pinfunction "2_2") (pintype "passive"))
      (node (ref "C73") (pin "1") (pinfunction "1_1") (pintype "passive"))
      (node (ref "C74") (pin "1") (pinfunction "1_1") (pintype "passive"))
      (node (ref "L2") (pin "1") (pinfunction "1_1") (pintype "passive"))
      (node (ref "U1") (pin "11") (pinfunction "AVDD_11") (pintype "passive"))
      (node (ref "U1") (pin "12") (pinfunction "AVDD_12") (pintype "passive"))
      (node (ref "U1") (pin "14") (pinfunction "AVDD_14") (pintype "passive"))
      (node (ref "U1") (pin "15") (pinfunction "AVDD_15") (pintype "passive"))
      (node (ref "U1") (pin "18") (pinfunction "AVDD_18") (pintype "passive"))
      (node (ref "U1") (pin "2") (pinfunction "AVDD_2") (pintype "passive"))
      (node (ref "U1") (pin "3") (pinfunction "AVDD_3") (pintype "passive"))
      (node (ref "U1") (pin "38") (pinfunction "AVDD_38") (pintype "passive"))
      (node (ref "U1") (pin "39") (pinfunction "AVDD_39") (pintype "passive"))
      (node (ref "U1") (pin "41") (pinfunction "AVDD_41") (pintype "passive"))
      (node (ref "U1") (pin "55") (pinfunction "AVDD_55") (pintype "passive"))
      (node (ref "U1") (pin "56") (pinfunction "AVDD_56") (pintype "passive"))
      (node (ref "U1") (pin "8") (pinfunction "AVDD_8") (pintype "passive"))
    )
    (net (code "46") (name "Net-(U1-INTn)") (class "Default")
      (node (ref "R285") (pin "2") (pinfunction "2_2") (pintype "passive"))
      (node (ref "U1") (pin "22") (pinfunction "INTn_22") (pintype "passive"))
    )
    (net (code "47") (name "Net-(U1-INTn_WOL)") (class "Default")
      (node (ref "R284") (pin "2") (pinfunction "2_2") (pintype "passive"))
      (node (ref "U1") (pin "23") (pinfunction "INTn_WOL_23") (pintype "passive"))
    )
    (net (code "48") (name "Net-(U1-TXN)") (class "Default")
      (node (ref "C112") (pin "1") (pinfunction "1_1") (pintype "passive"))
      (node (ref "U1") (pin "37") (pinfunction "TXN_37") (pintype "passive"))
    )
    (net (code "49") (name "Net-(U1-TXP)") (class "Default")
      (node (ref "C247") (pin "1") (pinfunction "1_1") (pintype "passive"))
      (node (ref "U1") (pin "36") (pinfunction "TXP_36") (pintype "passive"))
    )
    (net (code "50") (name "Net-(U1-XTLI)") (class "Default")
      (node (ref "C23") (pin "1") (pinfunction "1_1") (pintype "passive"))
      (node (ref "U1") (pin "20") (pinfunction "XTLI_20") (pintype "passive"))
      (node (ref "Y1") (pin "3") (pinfunction "3_3") (pintype "passive"))
    )
    (net (code "51") (name "Net-(U1-XTLO)") (class "Default")
      (node (ref "C24") (pin "1") (pinfunction "1_1") (pintype "passive"))
      (node (ref "U1") (pin "19") (pinfunction "XTLO_19") (pintype "passive"))
      (node (ref "Y1") (pin "1") (pinfunction "1_1") (pintype "passive"))
    )
    (net (code "52") (name "Net-(U1-XTL_SEL)") (class "Default")
      (node (ref "R84") (pin "1") (pinfunction "1_1") (pintype "passive"))
      (node (ref "U1") (pin "50") (pinfunction "XTL_SEL_50") (pintype "passive"))
    )
    (net (code "53") (name "unconnected-(U1-NC-Pad52)") (class "Default")
      (node (ref "U1") (pin "52") (pinfunction "NC_52") (pintype "passive+no_connect"))
    )
  )
)
